# Radio_TEA5767.net
KiCad netlist of a schematic drawn in EAGLE
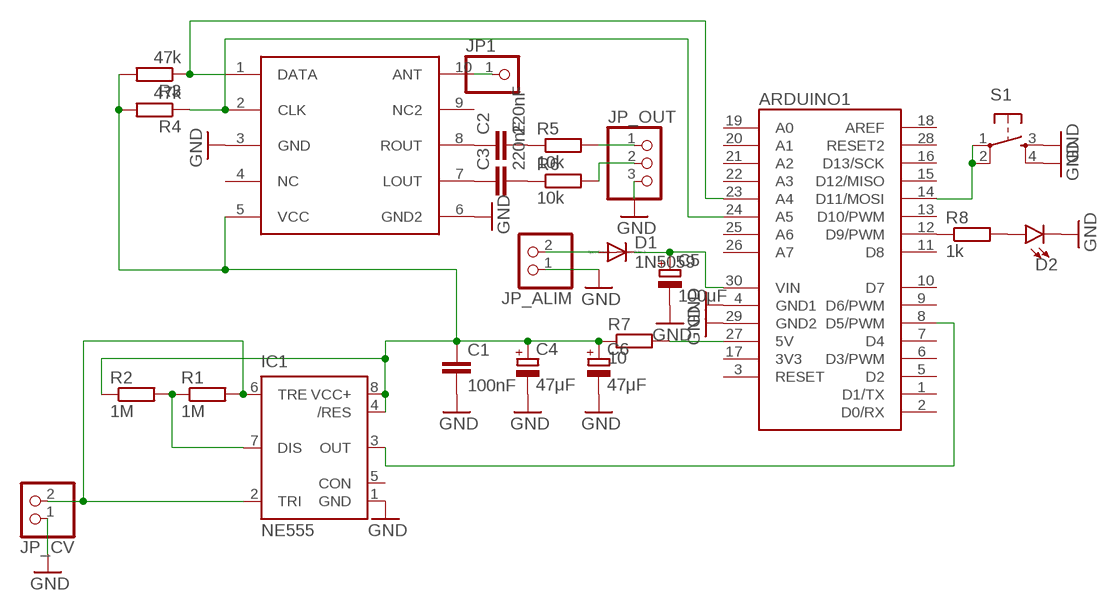
[diagram p0: schematic, sheet 1]

(export (version "E")
  (design (tool "Eeschema 10.0.6"))
  (components
    (comp (ref "ARDUINO1")
      (value "ARDUINO_NANO")
      (footprint "eagle-import:ARDUINO_NANO")
      (libsource (lib "eagle-import") (part "ARDUINO_NANO"))
    )
    (comp (ref "C1")
      (value "100nF")
      (footprint "eagle-import:C025-025X050")
      (libsource (lib "eagle-import") (part "C-EU025-025X050"))
    )
    (comp (ref "C2")
      (value "220nF")
      (footprint "eagle-import:C050-030X075")
      (libsource (lib "eagle-import") (part "C-EU050-030X075"))
    )
    (comp (ref "C3")
      (value "220nF")
      (footprint "eagle-import:C050-030X075")
      (libsource (lib "eagle-import") (part "C-EU050-030X075"))
    )
    (comp (ref "C4")
      (value "47μF")
      (footprint "eagle-import:E2,5-7")
      (libsource (lib "eagle-import") (part "CPOL-EUE2.5-7"))
    )
    (comp (ref "C5")
      (value "100μF")
      (footprint "eagle-import:E2,5-7")
      (libsource (lib "eagle-import") (part "CPOL-EUE2.5-7"))
    )
    (comp (ref "C6")
      (value "47μF")
      (footprint "eagle-import:E2,5-7")
      (libsource (lib "eagle-import") (part "CPOL-EUE2.5-7"))
    )
    (comp (ref "D1")
      (value "1N5059")
      (footprint "eagle-import:DO204-10")
      (libsource (lib "eagle-import") (part "1N5059"))
    )
    (comp (ref "D2")
      (value "LED3MM")
      (footprint "eagle-import:LED_3MM")
      (libsource (lib "eagle-import") (part "LED3MM"))
    )
    (comp (ref "IC1")
      (value "NE555")
      (footprint "eagle-import:DIL-08")
      (fields (field (name "MF") "Arrow Electronics") (field (name "MPN") "NE555N"))
      (libsource (lib "eagle-import") (part "NE555"))
    )
    (comp (ref "JP1")
      (value "PINHD-1X1")
      (footprint "eagle-import:1X01")
      (libsource (lib "eagle-import") (part "PINHD-1X1"))
    )
    (comp (ref "JP_ALIM")
      (value "PINHD-1X2")
      (footprint "eagle-import:1X02")
      (libsource (lib "eagle-import") (part "PINHD-1X2"))
    )
    (comp (ref "JP_CV")
      (value "PINHD-1X2")
      (footprint "eagle-import:1X02")
      (libsource (lib "eagle-import") (part "PINHD-1X2"))
    )
    (comp (ref "JP_OUT")
      (value "PINHD-1X3")
      (footprint "eagle-import:1X03")
      (libsource (lib "eagle-import") (part "PINHD-1X3"))
    )
    (comp (ref "R1")
      (value "1M")
      (footprint "eagle-import:0207_10")
      (libsource (lib "eagle-import") (part "R-EU_0207/10"))
    )
    (comp (ref "R2")
      (value "1M")
      (footprint "eagle-import:0207_10")
      (libsource (lib "eagle-import") (part "R-EU_0207/10"))
    )
    (comp (ref "R3")
      (value "47k")
      (footprint "eagle-import:0207_10")
      (libsource (lib "eagle-import") (part "R-EU_0207/10"))
    )
    (comp (ref "R4")
      (value "47k")
      (footprint "eagle-import:0207_10")
      (libsource (lib "eagle-import") (part "R-EU_0207/10"))
    )
    (comp (ref "R5")
      (value "10k")
      (footprint "eagle-import:0207_10")
      (libsource (lib "eagle-import") (part "R-EU_0207/10"))
    )
    (comp (ref "R6")
      (value "10k")
      (footprint "eagle-import:0207_10")
      (libsource (lib "eagle-import") (part "R-EU_0207/10"))
    )
    (comp (ref "R7")
      (value "10")
      (footprint "eagle-import:0207_10")
      (libsource (lib "eagle-import") (part "R-EU_0207/10"))
    )
    (comp (ref "R8")
      (value "1k")
      (footprint "eagle-import:0207_10")
      (libsource (lib "eagle-import") (part "R-EU_0207/10"))
    )
    (comp (ref "S1")
      (value "TAC_SWITCHPTH")
      (footprint "eagle-import:TACTILE-PTH")
      (libsource (lib "eagle-import") (part "TAC_SWITCHPTH"))
    )
    (comp (ref "U$1")
      (value "TEA5767")
      (footprint "eagle-import:RDA")
      (libsource (lib "eagle-import") (part "TEA5767"))
    )
  )
  (nets
    (net (code "1") (name "/3V3") (class "Default")
      (node (ref "ARDUINO1") (pin "17") (pinfunction "3V3_17") (pintype "power_in"))
    )
    (net (code "2") (name "/RESET2") (class "Default")
      (node (ref "ARDUINO1") (pin "28") (pinfunction "RESET2_28") (pintype "power_in"))
    )
    (net (code "3") (name "GND") (class "Default")
      (node (ref "ARDUINO1") (pin "29") (pinfunction "GND2_29") (pintype "power_in"))
      (node (ref "ARDUINO1") (pin "4") (pinfunction "GND1_4") (pintype "power_in"))
      (node (ref "C1") (pin "2") (pinfunction "2_2") (pintype "passive"))
      (node (ref "C4") (pin "-") (pinfunction "-_-") (pintype "passive"))
      (node (ref "C5") (pin "-") (pinfunction "-_-") (pintype "passive"))
      (node (ref "C6") (pin "-") (pinfunction "-_-") (pintype "passive"))
      (node (ref "D2") (pin "K") (pinfunction "C_K") (pintype "passive"))
      (node (ref "IC1") (pin "1") (pinfunction "GND_1") (pintype "power_in"))
      (node (ref "JP_ALIM") (pin "1") (pinfunction "1_1") (pintype "passive"))
      (node (ref "JP_CV") (pin "1") (pinfunction "1_1") (pintype "passive"))
      (node (ref "JP_OUT") (pin "3") (pinfunction "3_3") (pintype "passive"))
      (node (ref "S1") (pin "3") (pinfunction "3_3") (pintype "passive"))
      (node (ref "S1") (pin "4") (pinfunction "4_4") (pintype "passive"))
      (node (ref "U$1") (pin "3") (pinfunction "GND_3") (pintype "bidirectional"))
      (node (ref "U$1") (pin "6") (pinfunction "GND2_6") (pintype "bidirectional"))
    )
    (net (code "4") (name "Net-(ARDUINO1-5V)") (class "Default")
      (node (ref "ARDUINO1") (pin "27") (pinfunction "5V_27") (pintype "power_in"))
      (node (ref "R7") (pin "2") (pinfunction "2_2") (pintype "passive"))
    )
    (net (code "5") (name "Net-(ARDUINO1-A4)") (class "Default")
      (node (ref "ARDUINO1") (pin "23") (pinfunction "A4_23") (pintype "bidirectional"))
      (node (ref "R3") (pin "1") (pinfunction "1_1") (pintype "passive"))
      (node (ref "U$1") (pin "1") (pinfunction "DATA_1") (pintype "bidirectional"))
    )
    (net (code "6") (name "Net-(ARDUINO1-A5)") (class "Default")
      (node (ref "ARDUINO1") (pin "24") (pinfunction "A5_24") (pintype "bidirectional"))
      (node (ref "R4") (pin "1") (pinfunction "1_1") (pintype "passive"))
      (node (ref "U$1") (pin "2") (pinfunction "CLK_2") (pintype "bidirectional"))
    )
    (net (code "7") (name "Net-(ARDUINO1-D5{slash}PWM)") (class "Default")
      (node (ref "ARDUINO1") (pin "8") (pinfunction "D5/PWM_8") (pintype "bidirectional"))
      (node (ref "IC1") (pin "3") (pinfunction "OUT_3") (pintype "output"))
    )
    (net (code "8") (name "Net-(ARDUINO1-D9{slash}PWM)") (class "Default")
      (node (ref "ARDUINO1") (pin "12") (pinfunction "D9/PWM_12") (pintype "bidirectional"))
      (node (ref "R8") (pin "1") (pinfunction "1_1") (pintype "passive"))
    )
    (net (code "9") (name "Net-(ARDUINO1-D11{slash}MOSI)") (class "Default")
      (node (ref "ARDUINO1") (pin "14") (pinfunction "D11/MOSI_14") (pintype "bidirectional"))
      (node (ref "S1") (pin "1") (pinfunction "1_1") (pintype "passive"))
      (node (ref "S1") (pin "2") (pinfunction "2_2") (pintype "passive"))
    )
    (net (code "10") (name "Net-(ARDUINO1-VIN)") (class "Default")
      (node (ref "ARDUINO1") (pin "30") (pinfunction "VIN_30") (pintype "bidirectional"))
      (node (ref "C5") (pin "+") (pinfunction "+_+") (pintype "passive"))
      (node (ref "D1") (pin "C") (pinfunction "C_C") (pintype "passive"))
    )
    (net (code "11") (name "Net-(C2-Pad2)") (class "Default")
      (node (ref "C2") (pin "2") (pinfunction "2_2") (pintype "passive"))
      (node (ref "R5") (pin "1") (pinfunction "1_1") (pintype "passive"))
    )
    (net (code "12") (name "Net-(C3-Pad2)") (class "Default")
      (node (ref "C3") (pin "2") (pinfunction "2_2") (pintype "passive"))
      (node (ref "R6") (pin "1") (pinfunction "1_1") (pintype "passive"))
    )
    (net (code "13") (name "Net-(D1-PadA)") (class "Default")
      (node (ref "D1") (pin "A") (pinfunction "A_A") (pintype "passive"))
      (node (ref "JP_ALIM") (pin "2") (pinfunction "2_2") (pintype "passive"))
    )
    (net (code "14") (name "Net-(D2-PadA)") (class "Default")
      (node (ref "D2") (pin "A") (pinfunction "A_A") (pintype "passive"))
      (node (ref "R8") (pin "2") (pinfunction "2_2") (pintype "passive"))
    )
    (net (code "15") (name "Net-(IC1-DIS)") (class "Default")
      (node (ref "IC1") (pin "7") (pinfunction "DIS_7") (pintype "input"))
      (node (ref "R1") (pin "1") (pinfunction "1_1") (pintype "passive"))
      (node (ref "R2") (pin "2") (pinfunction "2_2") (pintype "passive"))
    )
    (net (code "16") (name "Net-(IC1-TRE)") (class "Default")
      (node (ref "IC1") (pin "2") (pinfunction "TRI_2") (pintype "input"))
      (node (ref "IC1") (pin "6") (pinfunction "TRE_6") (pintype "input"))
      (node (ref "JP_CV") (pin "2") (pinfunction "2_2") (pintype "passive"))
      (node (ref "R1") (pin "2") (pinfunction "2_2") (pintype "passive"))
    )
    (net (code "17") (name "Net-(IC1-VCC+)") (class "Default")
      (node (ref "C1") (pin "1") (pinfunction "1_1") (pintype "passive"))
      (node (ref "C4") (pin "+") (pinfunction "+_+") (pintype "passive"))
      (node (ref "C6") (pin "+") (pinfunction "+_+") (pintype "passive"))
      (node (ref "IC1") (pin "4") (pinfunction "/RES_4") (pintype "input"))
      (node (ref "IC1") (pin "8") (pinfunction "VCC+_8") (pintype "power_in"))
      (node (ref "R2") (pin "1") (pinfunction "1_1") (pintype "passive"))
      (node (ref "R3") (pin "2") (pinfunction "2_2") (pintype "passive"))
      (node (ref "R4") (pin "2") (pinfunction "2_2") (pintype "passive"))
      (node (ref "R7") (pin "1") (pinfunction "1_1") (pintype "passive"))
      (node (ref "U$1") (pin "5") (pinfunction "VCC_5") (pintype "bidirectional"))
    )
    (net (code "18") (name "Net-(JP_OUT-Pad1)") (class "Default")
      (node (ref "JP_OUT") (pin "1") (pinfunction "1_1") (pintype "passive"))
      (node (ref "R5") (pin "2") (pinfunction "2_2") (pintype "passive"))
    )
    (net (code "19") (name "Net-(JP_OUT-Pad2)") (class "Default")
      (node (ref "JP_OUT") (pin "2") (pinfunction "2_2") (pintype "passive"))
      (node (ref "R6") (pin "2") (pinfunction "2_2") (pintype "passive"))
    )
    (net (code "20") (name "Net-(U$1-ANT)") (class "Default")
      (node (ref "JP1") (pin "1") (pinfunction "1_1") (pintype "passive"))
      (node (ref "U$1") (pin "10") (pinfunction "ANT_10") (pintype "bidirectional"))
    )
    (net (code "21") (name "Net-(U$1-LOUT)") (class "Default")
      (node (ref "C3") (pin "1") (pinfunction "1_1") (pintype "passive"))
      (node (ref "U$1") (pin "7") (pinfunction "LOUT_7") (pintype "bidirectional"))
    )
    (net (code "22") (name "Net-(U$1-ROUT)") (class "Default")
      (node (ref "C2") (pin "1") (pinfunction "1_1") (pintype "passive"))
      (node (ref "U$1") (pin "8") (pinfunction "ROUT_8") (pintype "bidirectional"))
    )
    (net (code "23") (name "unconnected-(ARDUINO1-A0-Pad19)") (class "Default")
      (node (ref "ARDUINO1") (pin "19") (pinfunction "A0_19") (pintype "bidirectional"))
    )
    (net (code "24") (name "unconnected-(ARDUINO1-A1-Pad20)") (class "Default")
      (node (ref "ARDUINO1") (pin "20") (pinfunction "A1_20") (pintype "bidirectional"))
    )
    (net (code "25") (name "unconnected-(ARDUINO1-A2-Pad21)") (class "Default")
      (node (ref "ARDUINO1") (pin "21") (pinfunction "A2_21") (pintype "bidirectional"))
    )
    (net (code "26") (name "unconnected-(ARDUINO1-A3-Pad22)") (class "Default")
      (node (ref "ARDUINO1") (pin "22") (pinfunction "A3_22") (pintype "bidirectional"))
    )
    (net (code "27") (name "unconnected-(ARDUINO1-A6-Pad25)") (class "Default")
      (node (ref "ARDUINO1") (pin "25") (pinfunction "A6_25") (pintype "bidirectional"))
    )
    (net (code "28") (name "unconnected-(ARDUINO1-A7-Pad26)") (class "Default")
      (node (ref "ARDUINO1") (pin "26") (pinfunction "A7_26") (pintype "bidirectional"))
    )
    (net (code "29") (name "unconnected-(ARDUINO1-AREF-Pad18)") (class "Default")
      (node (ref "ARDUINO1") (pin "18") (pinfunction "AREF_18") (pintype "bidirectional"))
    )
    (net (code "30") (name "unconnected-(ARDUINO1-D0{slash}RX-Pad2)") (class "Default")
      (node (ref "ARDUINO1") (pin "2") (pinfunction "D0/RX_2") (pintype "bidirectional"))
    )
    (net (code "31") (name "unconnected-(ARDUINO1-D1{slash}TX-Pad1)") (class "Default")
      (node (ref "ARDUINO1") (pin "1") (pinfunction "D1/TX_1") (pintype "bidirectional"))
    )
    (net (code "32") (name "unconnected-(ARDUINO1-D2-Pad5)") (class "Default")
      (node (ref "ARDUINO1") (pin "5") (pinfunction "D2_5") (pintype "bidirectional"))
    )
    (net (code "33") (name "unconnected-(ARDUINO1-D3{slash}PWM-Pad6)") (class "Default")
      (node (ref "ARDUINO1") (pin "6") (pinfunction "D3/PWM_6") (pintype "bidirectional"))
    )
    (net (code "34") (name "unconnected-(ARDUINO1-D4-Pad7)") (class "Default")
      (node (ref "ARDUINO1") (pin "7") (pinfunction "D4_7") (pintype "bidirectional"))
    )
    (net (code "35") (name "unconnected-(ARDUINO1-D6{slash}PWM-Pad9)") (class "Default")
      (node (ref "ARDUINO1") (pin "9") (pinfunction "D6/PWM_9") (pintype "bidirectional"))
    )
    (net (code "36") (name "unconnected-(ARDUINO1-D7-Pad10)") (class "Default")
      (node (ref "ARDUINO1") (pin "10") (pinfunction "D7_10") (pintype "bidirectional"))
    )
    (net (code "37") (name "unconnected-(ARDUINO1-D8-Pad11)") (class "Default")
      (node (ref "ARDUINO1") (pin "11") (pinfunction "D8_11") (pintype "bidirectional"))
    )
    (net (code "38") (name "unconnected-(ARDUINO1-D10{slash}PWM-Pad13)") (class "Default")
      (node (ref "ARDUINO1") (pin "13") (pinfunction "D10/PWM_13") (pintype "bidirectional"))
    )
    (net (code "39") (name "unconnected-(ARDUINO1-D12{slash}MISO-Pad15)") (class "Default")
      (node (ref "ARDUINO1") (pin "15") (pinfunction "D12/MISO_15") (pintype "bidirectional"))
    )
    (net (code "40") (name "unconnected-(ARDUINO1-D13{slash}SCK-Pad16)") (class "Default")
      (node (ref "ARDUINO1") (pin "16") (pinfunction "D13/SCK_16") (pintype "bidirectional"))
    )
    (net (code "41") (name "unconnected-(ARDUINO1-RESET-Pad3)") (class "Default")
      (node (ref "ARDUINO1") (pin "3") (pinfunction "RESET_3") (pintype "bidirectional"))
    )
    (net (code "42") (name "unconnected-(IC1-CON-Pad5)") (class "Default")
      (node (ref "IC1") (pin "5") (pinfunction "CON_5") (pintype "input"))
    )
    (net (code "43") (name "unconnected-(U$1-NC-Pad4)") (class "Default")
      (node (ref "U$1") (pin "4") (pinfunction "NC_4") (pintype "bidirectional"))
    )
    (net (code "44") (name "unconnected-(U$1-NC2-Pad9)") (class "Default")
      (node (ref "U$1") (pin "9") (pinfunction "NC2_9") (pintype "bidirectional"))
    )
  )
)
